# hapcan-dali.net
KiCad netlist of a schematic drawn in EAGLE
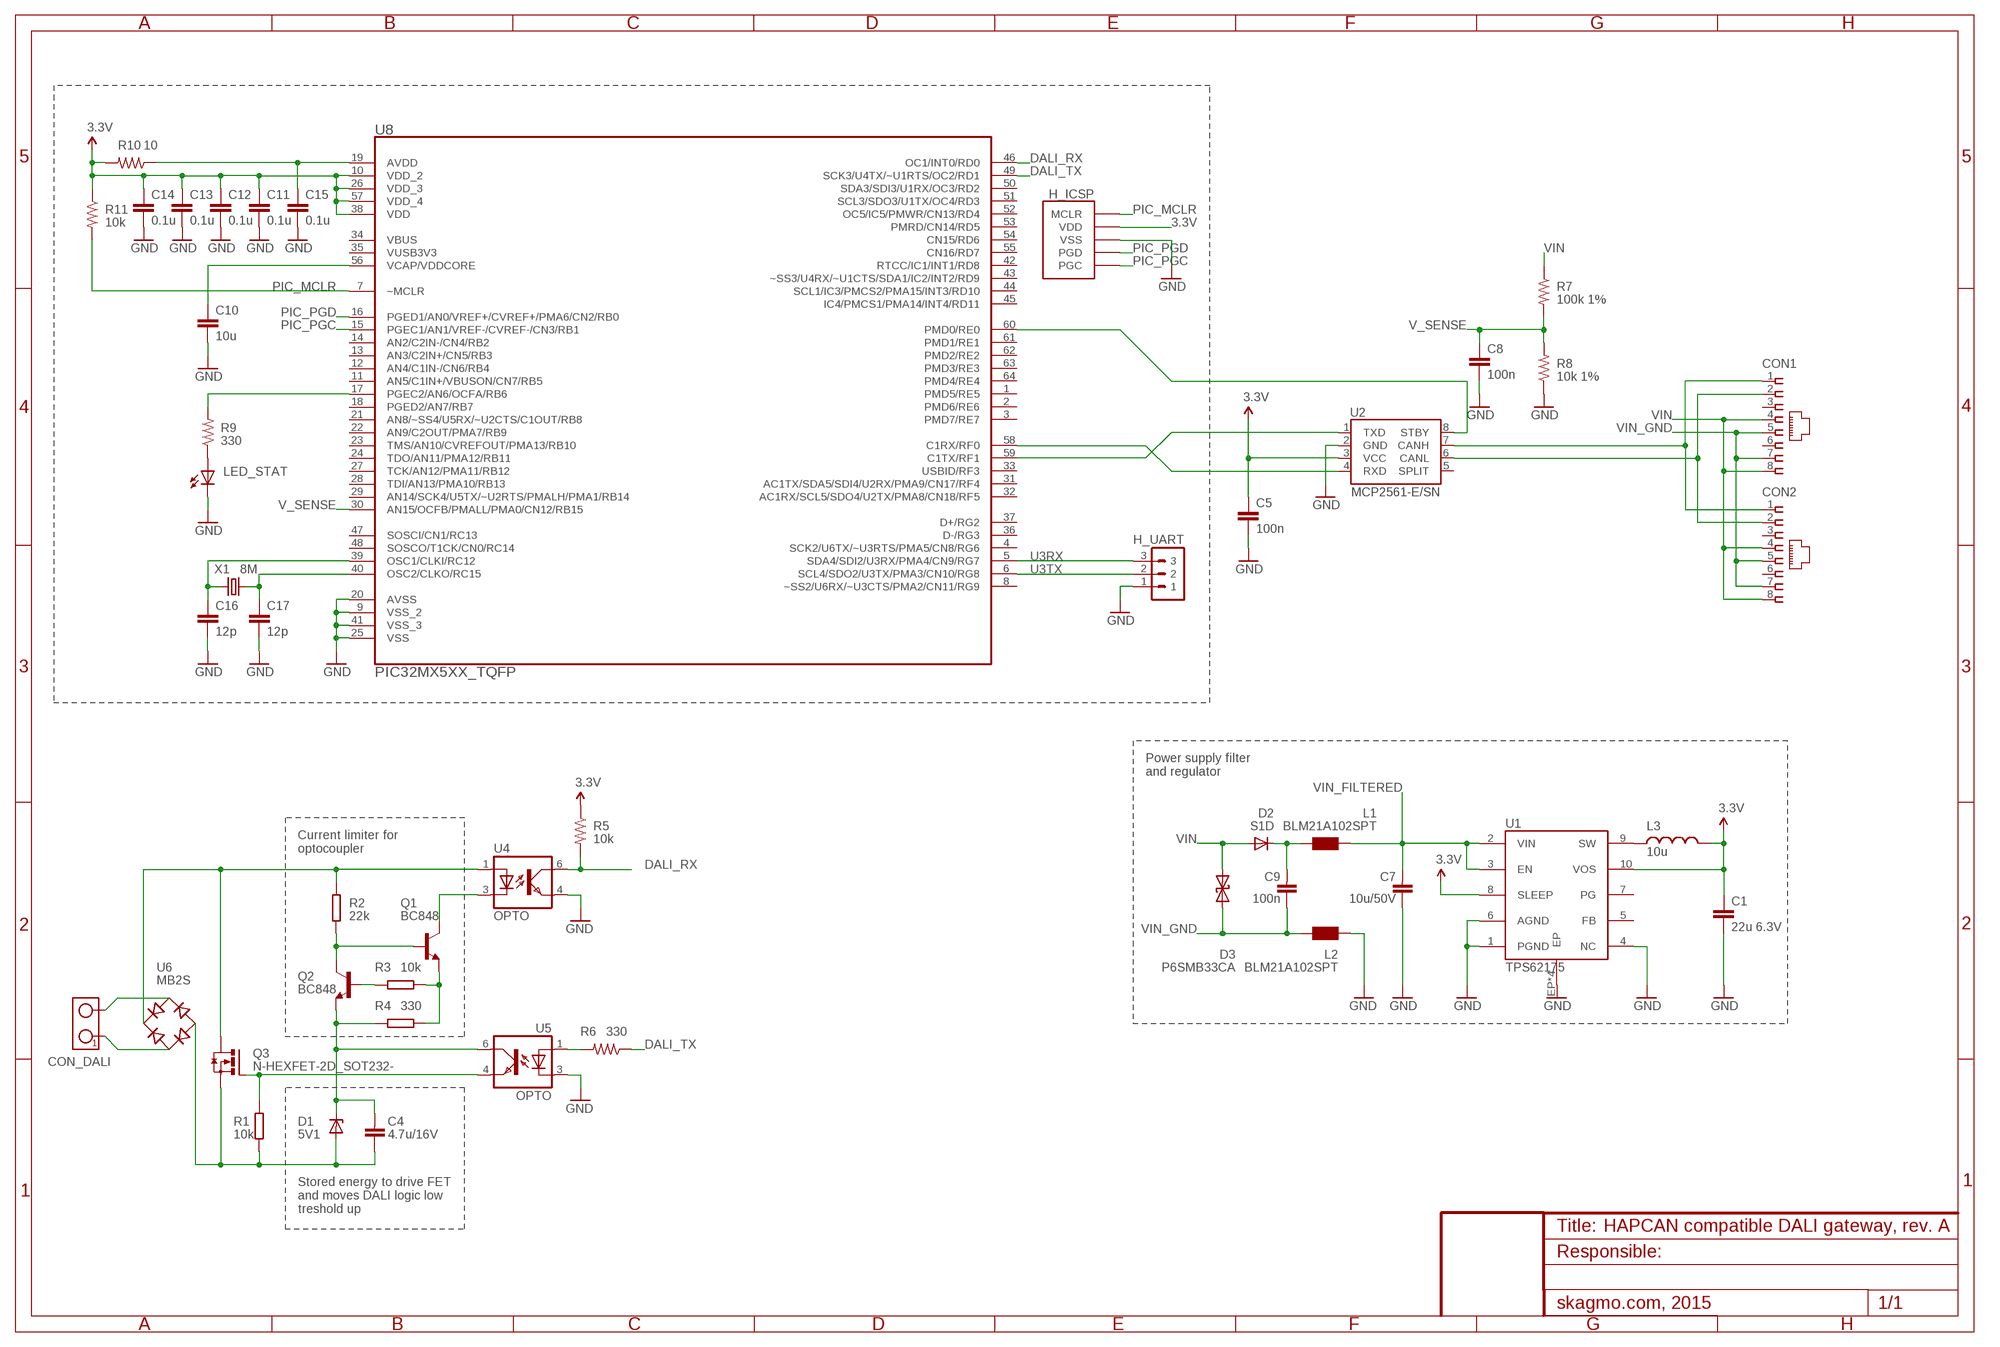
[diagram p0: schematic, sheet 1]

(export (version "E")
  (design (tool "Eeschema 10.0.6"))
  (components
    (comp (ref "C1")
      (value "22u 6.3V")
      (footprint "eagle-import:0805")
      (libsource (lib "eagle-import") (part "CAP0805"))
    )
    (comp (ref "C4")
      (value "4.7u/16V")
      (footprint "eagle-import:0805")
      (libsource (lib "eagle-import") (part "CAPACITOR0805"))
    )
    (comp (ref "C5")
      (value "100n")
      (footprint "eagle-import:0603")
      (libsource (lib "eagle-import") (part "CAP0603"))
    )
    (comp (ref "C7")
      (value "10u/50V")
      (footprint "eagle-import:1210")
      (libsource (lib "eagle-import") (part "CAPACITOR1210"))
    )
    (comp (ref "C8")
      (value "100n")
      (footprint "eagle-import:0603")
      (libsource (lib "eagle-import") (part "CAP0603"))
    )
    (comp (ref "C9")
      (value "100n")
      (footprint "eagle-import:0805")
      (libsource (lib "eagle-import") (part "CAPACITOR0805"))
    )
    (comp (ref "C10")
      (value "10u")
      (footprint "eagle-import:0805")
      (libsource (lib "eagle-import") (part "CAP0805"))
    )
    (comp (ref "C11")
      (value "0.1u")
      (footprint "eagle-import:0603")
      (libsource (lib "eagle-import") (part "CAP0603"))
    )
    (comp (ref "C12")
      (value "0.1u")
      (footprint "eagle-import:0603")
      (libsource (lib "eagle-import") (part "CAP0603"))
    )
    (comp (ref "C13")
      (value "0.1u")
      (footprint "eagle-import:0603")
      (libsource (lib "eagle-import") (part "CAP0603"))
    )
    (comp (ref "C14")
      (value "0.1u")
      (footprint "eagle-import:0603")
      (libsource (lib "eagle-import") (part "CAP0603"))
    )
    (comp (ref "C15")
      (value "0.1u")
      (footprint "eagle-import:0603")
      (libsource (lib "eagle-import") (part "CAP0603"))
    )
    (comp (ref "C16")
      (value "12p")
      (footprint "eagle-import:0603")
      (libsource (lib "eagle-import") (part "CAP0603"))
    )
    (comp (ref "C17")
      (value "12p")
      (footprint "eagle-import:0603")
      (libsource (lib "eagle-import") (part "CAP0603"))
    )
    (comp (ref "CON1")
      (value "RJ45-SOCKET")
      (footprint "eagle-import:RJ45-PCB-SOCKET")
      (libsource (lib "eagle-import") (part "RJ45-SOCKET"))
    )
    (comp (ref "CON2")
      (value "RJ45-SOCKET")
      (footprint "eagle-import:RJ45-PCB-SOCKET")
      (libsource (lib "eagle-import") (part "RJ45-SOCKET"))
    )
    (comp (ref "CON_DALI")
      (value "TERMINAL-2")
      (footprint "eagle-import:ARK2-5X10,5MM")
      (libsource (lib "eagle-import") (part "TERMINAL-2-5X10,5MM"))
    )
    (comp (ref "D1")
      (value "5V1")
      (footprint "eagle-import:SOT23")
      (libsource (lib "eagle-import") (part "ZENER-DIODESOT23"))
    )
    (comp (ref "D2")
      (value "S1D")
      (footprint "eagle-import:DO-214")
      (libsource (lib "eagle-import") (part "DIODE_DO-214"))
    )
    (comp (ref "D3")
      (value "P6SMB33CA")
      (footprint "eagle-import:DO-214_TRANSIL2")
      (libsource (lib "eagle-import") (part "DIODE_TRANSIL2"))
    )
    (comp (ref "H_ICSP")
      (value "H1X5_ICSP")
      (footprint "eagle-import:H1X5_2MM")
      (libsource (lib "eagle-import") (part "H1X5_ICSP"))
    )
    (comp (ref "H_UART")
      (value "H1X3_XH")
      (footprint "eagle-import:CON_B3B-XH-A")
      (libsource (lib "eagle-import") (part "H1X3_XH"))
    )
    (comp (ref "L1")
      (value "BLM21A102SPT")
      (footprint "eagle-import:0805")
      (libsource (lib "eagle-import") (part "CHOKE0805"))
    )
    (comp (ref "L2")
      (value "BLM21A102SPT")
      (footprint "eagle-import:0805")
      (libsource (lib "eagle-import") (part "CHOKE0805"))
    )
    (comp (ref "L3")
      (value "10u")
      (footprint "eagle-import:IND-SRN3015")
      (libsource (lib "eagle-import") (part "INDUCTOR_SRN3015"))
    )
    (comp (ref "LED_STAT")
      (value "LEDCHIPLED_0805")
      (footprint "eagle-import:CHIPLED_0805")
      (libsource (lib "eagle-import") (part "LEDCHIPLED_0805"))
    )
    (comp (ref "Q1")
      (value "BC848")
      (footprint "eagle-import:SOT23")
      (libsource (lib "eagle-import") (part "BC848"))
    )
    (comp (ref "Q2")
      (value "BC848")
      (footprint "eagle-import:SOT23")
      (libsource (lib "eagle-import") (part "BC848"))
    )
    (comp (ref "Q3")
      (value "N-HEXFET-2D_SOT232-")
      (footprint "eagle-import:SOT223")
      (libsource (lib "eagle-import") (part "N-HEXFET-2D_?-SOT232"))
    )
    (comp (ref "R1")
      (value "10k")
      (footprint "eagle-import:0805")
      (libsource (lib "eagle-import") (part "HAPCAN_devices - UNIV3_RESISTOR0805"))
    )
    (comp (ref "R2")
      (value "22k")
      (footprint "eagle-import:0805")
      (libsource (lib "eagle-import") (part "HAPCAN_devices - UNIV3_RESISTOR0805"))
    )
    (comp (ref "R3")
      (value "10k")
      (footprint "eagle-import:0805")
      (libsource (lib "eagle-import") (part "HAPCAN_devices - UNIV3_RESISTOR0805"))
    )
    (comp (ref "R4")
      (value "330")
      (footprint "eagle-import:0805")
      (libsource (lib "eagle-import") (part "HAPCAN_devices - UNIV3_RESISTOR0805"))
    )
    (comp (ref "R5")
      (value "10k")
      (footprint "eagle-import:0603")
      (libsource (lib "eagle-import") (part "RESISTOR0603"))
    )
    (comp (ref "R6")
      (value "330")
      (footprint "eagle-import:0603")
      (libsource (lib "eagle-import") (part "RESISTOR0603"))
    )
    (comp (ref "R7")
      (value "100k 1%")
      (footprint "eagle-import:0603")
      (libsource (lib "eagle-import") (part "RESISTOR0603"))
    )
    (comp (ref "R8")
      (value "10k 1%")
      (footprint "eagle-import:0603")
      (libsource (lib "eagle-import") (part "RESISTOR0603"))
    )
    (comp (ref "R9")
      (value "330")
      (footprint "eagle-import:0603")
      (libsource (lib "eagle-import") (part "RESISTOR0603"))
    )
    (comp (ref "R10")
      (value "10")
      (footprint "eagle-import:0603")
      (libsource (lib "eagle-import") (part "RESISTOR0603"))
    )
    (comp (ref "R11")
      (value "10k")
      (footprint "eagle-import:0603")
      (libsource (lib "eagle-import") (part "RESISTOR0603"))
    )
    (comp (ref "U1")
      (value "TPS62175")
      (footprint "eagle-import:WSON-10")
      (libsource (lib "eagle-import") (part "TPS62175"))
    )
    (comp (ref "U2")
      (value "MCP2561-E/SN")
      (footprint "eagle-import:SO-08")
      (libsource (lib "eagle-import") (part "MCP2561-E/SN"))
    )
    (comp (ref "U4")
      (value "OPTO")
      (footprint "eagle-import:TLP185")
      (libsource (lib "eagle-import") (part "OPTO"))
    )
    (comp (ref "U5")
      (value "OPTO")
      (footprint "eagle-import:TLP185")
      (libsource (lib "eagle-import") (part "OPTO"))
    )
    (comp (ref "U6")
      (value "MB2S")
      (footprint "eagle-import:SOIC-4")
      (libsource (lib "eagle-import") (part "MBS2"))
    )
    (comp (ref "U8")
      (value "PIC32MX5XX_TQFP")
      (footprint "eagle-import:TQFP64")
      (libsource (lib "eagle-import") (part "PIC32MX5XX_TQFP"))
    )
    (comp (ref "X1")
      (value "8M")
      (footprint "eagle-import:TXC-7A")
      (libsource (lib "eagle-import") (part "CRYSTAL_TXC-7A"))
    )
  )
  (nets
    (net (code "1") (name "/DALI_RX") (class "Default")
      (node (ref "R5") (pin "2") (pinfunction "2_2") (pintype "passive"))
      (node (ref "U4") (pin "6") (pinfunction "COL_6") (pintype "passive"))
      (node (ref "U8") (pin "46") (pinfunction "OC1/INT0/RD0_46") (pintype "bidirectional"))
    )
    (net (code "2") (name "/DALI_TX") (class "Default")
      (node (ref "R6") (pin "1") (pinfunction "1_1") (pintype "passive"))
      (node (ref "U8") (pin "49") (pinfunction "SCK3/U4TX/~{U1RTS/OC2/RD1}_49") (pintype "bidirectional"))
    )
    (net (code "3") (name "/PIC_MCLR") (class "Default")
      (node (ref "H_ICSP") (pin "1") (pinfunction "MCLR_1") (pintype "bidirectional"))
      (node (ref "R11") (pin "2") (pinfunction "2_2") (pintype "passive"))
      (node (ref "U8") (pin "7") (pinfunction "~{MCLR}_7") (pintype "input"))
    )
    (net (code "4") (name "/PIC_PGC") (class "Default")
      (node (ref "H_ICSP") (pin "5") (pinfunction "PGC_5") (pintype "bidirectional"))
      (node (ref "U8") (pin "15") (pinfunction "PGEC1/AN1/VREF-/CVREF-/CN3/RB1_15") (pintype "bidirectional"))
    )
    (net (code "5") (name "/PIC_PGD") (class "Default")
      (node (ref "H_ICSP") (pin "4") (pinfunction "PGD_4") (pintype "bidirectional"))
      (node (ref "U8") (pin "16") (pinfunction "PGED1/AN0/VREF+/CVREF+/PMA6/CN2/RB0_16") (pintype "bidirectional"))
    )
    (net (code "6") (name "/U3RX") (class "Default")
      (node (ref "H_UART") (pin "3") (pinfunction "3_3") (pintype "passive"))
      (node (ref "U8") (pin "5") (pinfunction "SDA4/SDI2/U3RX/PMA4/CN9/RG7_5") (pintype "bidirectional"))
    )
    (net (code "7") (name "/U3TX") (class "Default")
      (node (ref "H_UART") (pin "2") (pinfunction "2_2") (pintype "passive"))
      (node (ref "U8") (pin "6") (pinfunction "SCL4/SDO2/U3TX/PMA3/CN10/RG8_6") (pintype "bidirectional"))
    )
    (net (code "8") (name "/VIN") (class "Default")
      (node (ref "CON1") (pin "4") (pinfunction "4_4") (pintype "passive"))
      (node (ref "CON1") (pin "8") (pinfunction "8_8") (pintype "passive"))
      (node (ref "CON2") (pin "4") (pinfunction "4_4") (pintype "passive"))
      (node (ref "CON2") (pin "8") (pinfunction "8_8") (pintype "passive"))
      (node (ref "D2") (pin "A") (pinfunction "A_A") (pintype "passive"))
      (node (ref "D3") (pin "C") (pinfunction "2_C") (pintype "passive"))
      (node (ref "R7") (pin "1") (pinfunction "1_1") (pintype "passive"))
    )
    (net (code "9") (name "/VIN_FILTERED") (class "Default")
      (node (ref "C7") (pin "1") (pinfunction "1_1") (pintype "passive"))
      (node (ref "L1") (pin "1") (pinfunction "1_1") (pintype "passive"))
      (node (ref "U1") (pin "2") (pinfunction "VIN_2") (pintype "bidirectional"))
      (node (ref "U1") (pin "3") (pinfunction "EN_3") (pintype "bidirectional"))
    )
    (net (code "10") (name "/VIN_GND") (class "Default")
      (node (ref "C9") (pin "2") (pinfunction "2_2") (pintype "passive"))
      (node (ref "CON1") (pin "5") (pinfunction "5_5") (pintype "passive"))
      (node (ref "CON1") (pin "7") (pinfunction "7_7") (pintype "passive"))
      (node (ref "CON2") (pin "5") (pinfunction "5_5") (pintype "passive"))
      (node (ref "CON2") (pin "7") (pinfunction "7_7") (pintype "passive"))
      (node (ref "D3") (pin "A") (pinfunction "1_A") (pintype "passive"))
      (node (ref "L2") (pin "2") (pinfunction "2_2") (pintype "passive"))
    )
    (net (code "11") (name "/VUSB3V3") (class "Default")
      (node (ref "U8") (pin "35") (pinfunction "VUSB3V3_35") (pintype "power_in"))
    )
    (net (code "12") (name "/V_SENSE") (class "Default")
      (node (ref "C8") (pin "1") (pinfunction "1_1") (pintype "passive"))
      (node (ref "R7") (pin "2") (pinfunction "2_2") (pintype "passive"))
      (node (ref "R8") (pin "2") (pinfunction "2_2") (pintype "passive"))
      (node (ref "U8") (pin "30") (pinfunction "AN15/OCFB/PMALL/PMA0/CN12/RB15_30") (pintype "bidirectional"))
    )
    (net (code "13") (name "3.3V") (class "Default")
      (node (ref "C1") (pin "1") (pinfunction "1_1") (pintype "passive"))
      (node (ref "C11") (pin "1") (pinfunction "1_1") (pintype "passive"))
      (node (ref "C12") (pin "1") (pinfunction "1_1") (pintype "passive"))
      (node (ref "C13") (pin "1") (pinfunction "1_1") (pintype "passive"))
      (node (ref "C14") (pin "1") (pinfunction "1_1") (pintype "passive"))
      (node (ref "C5") (pin "1") (pinfunction "1_1") (pintype "passive"))
      (node (ref "H_ICSP") (pin "2") (pinfunction "VDD_2") (pintype "power_in"))
      (node (ref "L3") (pin "P$2") (pinfunction "2_P$2") (pintype "passive"))
      (node (ref "R10") (pin "2") (pinfunction "2_2") (pintype "passive"))
      (node (ref "R11") (pin "1") (pinfunction "1_1") (pintype "passive"))
      (node (ref "R5") (pin "1") (pinfunction "1_1") (pintype "passive"))
      (node (ref "U1") (pin "10") (pinfunction "VOS_10") (pintype "bidirectional"))
      (node (ref "U1") (pin "8") (pinfunction "SLEEP_8") (pintype "bidirectional"))
      (node (ref "U2") (pin "3") (pinfunction "VCC_3") (pintype "bidirectional"))
      (node (ref "U8") (pin "10") (pinfunction "VDD_2_10") (pintype "power_in"))
      (node (ref "U8") (pin "26") (pinfunction "VDD_3_26") (pintype "power_in"))
      (node (ref "U8") (pin "38") (pinfunction "VDD_38") (pintype "power_in"))
      (node (ref "U8") (pin "57") (pinfunction "VDD_4_57") (pintype "power_in"))
    )
    (net (code "14") (name "GND") (class "Default")
      (node (ref "C1") (pin "2") (pinfunction "2_2") (pintype "passive"))
      (node (ref "C10") (pin "2") (pinfunction "2_2") (pintype "passive"))
      (node (ref "C11") (pin "2") (pinfunction "2_2") (pintype "passive"))
      (node (ref "C12") (pin "2") (pinfunction "2_2") (pintype "passive"))
      (node (ref "C13") (pin "2") (pinfunction "2_2") (pintype "passive"))
      (node (ref "C14") (pin "2") (pinfunction "2_2") (pintype "passive"))
      (node (ref "C15") (pin "2") (pinfunction "2_2") (pintype "passive"))
      (node (ref "C16") (pin "2") (pinfunction "2_2") (pintype "passive"))
      (node (ref "C17") (pin "2") (pinfunction "2_2") (pintype "passive"))
      (node (ref "C5") (pin "2") (pinfunction "2_2") (pintype "passive"))
      (node (ref "C7") (pin "2") (pinfunction "2_2") (pintype "passive"))
      (node (ref "C8") (pin "2") (pinfunction "2_2") (pintype "passive"))
      (node (ref "H_ICSP") (pin "3") (pinfunction "VSS_3") (pintype "power_in"))
      (node (ref "H_UART") (pin "1") (pinfunction "1_1") (pintype "passive"))
      (node (ref "L2") (pin "1") (pinfunction "1_1") (pintype "passive"))
      (node (ref "LED_STAT") (pin "C") (pinfunction "C_C") (pintype "passive"))
      (node (ref "R8") (pin "1") (pinfunction "1_1") (pintype "passive"))
      (node (ref "U1") (pin "1") (pinfunction "PGND_1") (pintype "bidirectional"))
      (node (ref "U1") (pin "4") (pinfunction "NC_4") (pintype "bidirectional"))
      (node (ref "U1") (pin "6") (pinfunction "AGND_6") (pintype "bidirectional"))
      (node (ref "U1") (pin "EP") (pinfunction "EP_EP") (pintype "bidirectional"))
      (node (ref "U1") (pin "V1") (pinfunction "EP_V1") (pintype "bidirectional"))
      (node (ref "U1") (pin "V2") (pinfunction "EP_V2") (pintype "bidirectional"))
      (node (ref "U1") (pin "V3") (pinfunction "EP_V3") (pintype "bidirectional"))
      (node (ref "U2") (pin "2") (pinfunction "GND_2") (pintype "bidirectional"))
      (node (ref "U4") (pin "4") (pinfunction "EMIT_4") (pintype "passive"))
      (node (ref "U5") (pin "3") (pinfunction "C_3") (pintype "passive"))
      (node (ref "U8") (pin "20") (pinfunction "AVSS_20") (pintype "passive"))
      (node (ref "U8") (pin "25") (pinfunction "VSS_25") (pintype "passive"))
      (node (ref "U8") (pin "41") (pinfunction "VSS_3_41") (pintype "passive"))
      (node (ref "U8") (pin "9") (pinfunction "VSS_2_9") (pintype "passive"))
    )
    (net (code "15") (name "Net-(C9-Pad1)") (class "Default")
      (node (ref "C9") (pin "1") (pinfunction "1_1") (pintype "passive"))
      (node (ref "D2") (pin "C") (pinfunction "C_C") (pintype "passive"))
      (node (ref "L1") (pin "2") (pinfunction "2_2") (pintype "passive"))
    )
    (net (code "16") (name "Net-(D1-A)") (class "Default")
      (node (ref "C4") (pin "2") (pinfunction "2_2") (pintype "passive"))
      (node (ref "D1") (pin "1") (pinfunction "A_1") (pintype "passive"))
      (node (ref "Q3") (pin "3") (pinfunction "S_3") (pintype "passive"))
      (node (ref "R1") (pin "1") (pinfunction "1_1") (pintype "passive"))
      (node (ref "U6") (pin "-") (pinfunction "-_-") (pintype "passive"))
    )
    (net (code "17") (name "Net-(D1-C)") (class "Default")
      (node (ref "C4") (pin "1") (pinfunction "1_1") (pintype "passive"))
      (node (ref "D1") (pin "3") (pinfunction "C_3") (pintype "passive"))
      (node (ref "Q2") (pin "2") (pinfunction "E_2") (pintype "passive"))
      (node (ref "R4") (pin "1") (pinfunction "1_1") (pintype "passive"))
      (node (ref "U5") (pin "6") (pinfunction "COL_6") (pintype "passive"))
    )
    (net (code "18") (name "Net-(L3-1)") (class "Default")
      (node (ref "L3") (pin "P$1") (pinfunction "1_P$1") (pintype "passive"))
      (node (ref "U1") (pin "9") (pinfunction "SW_9") (pintype "bidirectional"))
    )
    (net (code "19") (name "Net-(LED_STAT-PadA)") (class "Default")
      (node (ref "LED_STAT") (pin "A") (pinfunction "A_A") (pintype "passive"))
      (node (ref "R9") (pin "1") (pinfunction "1_1") (pintype "passive"))
    )
    (net (code "20") (name "Net-(Q1-B)") (class "Default")
      (node (ref "Q1") (pin "1") (pinfunction "B_1") (pintype "passive"))
      (node (ref "Q2") (pin "3") (pinfunction "C_3") (pintype "passive"))
      (node (ref "R2") (pin "1") (pinfunction "1_1") (pintype "passive"))
    )
    (net (code "21") (name "Net-(Q1-C)") (class "Default")
      (node (ref "Q1") (pin "3") (pinfunction "C_3") (pintype "passive"))
      (node (ref "U4") (pin "3") (pinfunction "C_3") (pintype "passive"))
    )
    (net (code "22") (name "Net-(Q1-E)") (class "Default")
      (node (ref "Q1") (pin "2") (pinfunction "E_2") (pintype "passive"))
      (node (ref "R3") (pin "1") (pinfunction "1_1") (pintype "passive"))
      (node (ref "R4") (pin "2") (pinfunction "2_2") (pintype "passive"))
    )
    (net (code "23") (name "Net-(Q2-B)") (class "Default")
      (node (ref "Q2") (pin "1") (pinfunction "B_1") (pintype "passive"))
      (node (ref "R3") (pin "2") (pinfunction "2_2") (pintype "passive"))
    )
    (net (code "24") (name "Net-(Q3-G)") (class "Default")
      (node (ref "Q3") (pin "1") (pinfunction "G_1") (pintype "passive"))
      (node (ref "R1") (pin "2") (pinfunction "2_2") (pintype "passive"))
      (node (ref "U5") (pin "4") (pinfunction "EMIT_4") (pintype "passive"))
    )
    (net (code "25") (name "Net-(U2-CANH)") (class "Default")
      (node (ref "CON1") (pin "1") (pinfunction "1_1") (pintype "passive"))
      (node (ref "CON2") (pin "1") (pinfunction "1_1") (pintype "passive"))
      (node (ref "U2") (pin "7") (pinfunction "CANH_7") (pintype "bidirectional"))
    )
    (net (code "26") (name "Net-(U2-CANL)") (class "Default")
      (node (ref "CON1") (pin "2") (pinfunction "2_2") (pintype "passive"))
      (node (ref "CON2") (pin "2") (pinfunction "2_2") (pintype "passive"))
      (node (ref "U2") (pin "6") (pinfunction "CANL_6") (pintype "bidirectional"))
    )
    (net (code "27") (name "Net-(U2-RXD)") (class "Default")
      (node (ref "U2") (pin "4") (pinfunction "RXD_4") (pintype "bidirectional"))
      (node (ref "U8") (pin "58") (pinfunction "C1RX/RF0_58") (pintype "bidirectional"))
    )
    (net (code "28") (name "Net-(U2-STBY)") (class "Default")
      (node (ref "U2") (pin "8") (pinfunction "STBY_8") (pintype "bidirectional"))
      (node (ref "U8") (pin "60") (pinfunction "PMD0/RE0_60") (pintype "bidirectional"))
    )
    (net (code "29") (name "Net-(U2-TXD)") (class "Default")
      (node (ref "U2") (pin "1") (pinfunction "TXD_1") (pintype "bidirectional"))
      (node (ref "U8") (pin "59") (pinfunction "C1TX/RF1_59") (pintype "bidirectional"))
    )
    (net (code "30") (name "Net-(U4-A)") (class "Default")
      (node (ref "Q3") (pin "2") (pinfunction "D_2") (pintype "passive"))
      (node (ref "Q3") (pin "4") (pinfunction "D_4") (pintype "passive"))
      (node (ref "R2") (pin "2") (pinfunction "2_2") (pintype "passive"))
      (node (ref "U4") (pin "1") (pinfunction "A_1") (pintype "passive"))
      (node (ref "U6") (pin "+") (pinfunction "+_+") (pintype "passive"))
    )
    (net (code "31") (name "Net-(U5-A)") (class "Default")
      (node (ref "R6") (pin "2") (pinfunction "2_2") (pintype "passive"))
      (node (ref "U5") (pin "1") (pinfunction "A_1") (pintype "passive"))
    )
    (net (code "32") (name "Net-(U6-AC1)") (class "Default")
      (node (ref "CON_DALI") (pin "1") (pinfunction "1_1") (pintype "passive"))
      (node (ref "U6") (pin "~1") (pinfunction "AC1_~1") (pintype "passive"))
    )
    (net (code "33") (name "Net-(U6-AC2)") (class "Default")
      (node (ref "CON_DALI") (pin "2") (pinfunction "2_2") (pintype "passive"))
      (node (ref "U6") (pin "~2") (pinfunction "AC2_~2") (pintype "passive"))
    )
    (net (code "34") (name "Net-(U8-AVDD)") (class "Default")
      (node (ref "C15") (pin "1") (pinfunction "1_1") (pintype "passive"))
      (node (ref "R10") (pin "1") (pinfunction "1_1") (pintype "passive"))
      (node (ref "U8") (pin "19") (pinfunction "AVDD_19") (pintype "power_in"))
    )
    (net (code "35") (name "Net-(U8-OSC1{slash}CLKI{slash}RC12)") (class "Default")
      (node (ref "C16") (pin "1") (pinfunction "1_1") (pintype "passive"))
      (node (ref "U8") (pin "39") (pinfunction "OSC1/CLKI/RC12_39") (pintype "bidirectional"))
      (node (ref "X1") (pin "1") (pinfunction "1_1") (pintype "passive"))
    )
    (net (code "36") (name "Net-(U8-OSC2{slash}CLKO{slash}RC15)") (class "Default")
      (node (ref "C17") (pin "1") (pinfunction "1_1") (pintype "passive"))
      (node (ref "U8") (pin "40") (pinfunction "OSC2/CLKO/RC15_40") (pintype "bidirectional"))
      (node (ref "X1") (pin "2") (pinfunction "2_2") (pintype "passive"))
    )
    (net (code "37") (name "Net-(U8-PGEC2{slash}AN6{slash}OCFA{slash}RB6)") (class "Default")
      (node (ref "R9") (pin "2") (pinfunction "2_2") (pintype "passive"))
      (node (ref "U8") (pin "17") (pinfunction "PGEC2/AN6/OCFA/RB6_17") (pintype "bidirectional"))
    )
    (net (code "38") (name "Net-(U8-VCAP{slash}VDDCORE)") (class "Default")
      (node (ref "C10") (pin "1") (pinfunction "1_1") (pintype "passive"))
      (node (ref "U8") (pin "56") (pinfunction "VCAP/VDDCORE_56") (pintype "power_in"))
    )
    (net (code "39") (name "unconnected-(CON1-Pad3)") (class "Default")
      (node (ref "CON1") (pin "3") (pinfunction "3_3") (pintype "passive"))
    )
    (net (code "40") (name "unconnected-(CON1-Pad6)") (class "Default")
      (node (ref "CON1") (pin "6") (pinfunction "6_6") (pintype "passive"))
    )
    (net (code "41") (name "unconnected-(CON2-Pad3)") (class "Default")
      (node (ref "CON2") (pin "3") (pinfunction "3_3") (pintype "passive"))
    )
    (net (code "42") (name "unconnected-(CON2-Pad6)") (class "Default")
      (node (ref "CON2") (pin "6") (pinfunction "6_6") (pintype "passive"))
    )
    (net (code "43") (name "unconnected-(U1-FB-Pad5)") (class "Default")
      (node (ref "U1") (pin "5") (pinfunction "FB_5") (pintype "bidirectional"))
    )
    (net (code "44") (name "unconnected-(U1-PG-Pad7)") (class "Default")
      (node (ref "U1") (pin "7") (pinfunction "PG_7") (pintype "bidirectional"))
    )
    (net (code "45") (name "unconnected-(U2-SPLIT-Pad5)") (class "Default")
      (node (ref "U2") (pin "5") (pinfunction "SPLIT_5") (pintype "bidirectional"))
    )
    (net (code "46") (name "unconnected-(U8-AC1RX{slash}SCL5{slash}SDO4{slash}U2TX{slash}PMA8{slash}CN18{slash}RF5-Pad32)") (class "Default")
      (node (ref "U8") (pin "32") (pinfunction "AC1RX/SCL5/SDO4/U2TX/PMA8/CN18/RF5_32") (pintype "bidirectional"))
    )
    (net (code "47") (name "unconnected-(U8-AC1TX{slash}SDA5{slash}SDI4{slash}U2RX{slash}PMA9{slash}CN17{slash}RF4-Pad31)") (class "Default")
      (node (ref "U8") (pin "31") (pinfunction "AC1TX/SDA5/SDI4/U2RX/PMA9/CN17/RF4_31") (pintype "bidirectional"))
    )
    (net (code "48") (name "unconnected-(U8-AN2{slash}C2IN-{slash}CN4{slash}RB2-Pad14)") (class "Default")
      (node (ref "U8") (pin "14") (pinfunction "AN2/C2IN-/CN4/RB2_14") (pintype "bidirectional"))
    )
    (net (code "49") (name "unconnected-(U8-AN3{slash}C2IN+{slash}CN5{slash}RB3-Pad13)") (class "Default")
      (node (ref "U8") (pin "13") (pinfunction "AN3/C2IN+/CN5/RB3_13") (pintype "bidirectional"))
    )
    (net (code "50") (name "unconnected-(U8-AN4{slash}C1IN-{slash}CN6{slash}RB4-Pad12)") (class "Default")
      (node (ref "U8") (pin "12") (pinfunction "AN4/C1IN-/CN6/RB4_12") (pintype "bidirectional"))
    )
    (net (code "51") (name "unconnected-(U8-AN5{slash}C1IN+{slash}VBUSON{slash}CN7{slash}RB5-Pad11)") (class "Default")
      (node (ref "U8") (pin "11") (pinfunction "AN5/C1IN+/VBUSON/CN7/RB5_11") (pintype "bidirectional"))
    )
    (net (code "52") (name "unconnected-(U8-AN8{slash}~{SS4{slash}U5RX{slash}}U2CTS{slash}C1OUT{slash}RB8-Pad21)") (class "Default")
      (node (ref "U8") (pin "21") (pinfunction "AN8/~{SS4/U5RX/}U2CTS/C1OUT/RB8_21") (pintype "bidirectional"))
    )
    (net (code "53") (name "unconnected-(U8-AN9{slash}C2OUT{slash}PMA7{slash}RB9-Pad22)") (class "Default")
      (node (ref "U8") (pin "22") (pinfunction "AN9/C2OUT/PMA7/RB9_22") (pintype "bidirectional"))
    )
    (net (code "54") (name "unconnected-(U8-AN14{slash}SCK4{slash}U5TX{slash}~{U2RTS{slash}PMALH{slash}PMA1{slash}RB14}-Pad29)") (class "Default")
      (node (ref "U8") (pin "29") (pinfunction "AN14/SCK4/U5TX/~{U2RTS/PMALH/PMA1/RB14}_29") (pintype "bidirectional"))
    )
    (net (code "55") (name "unconnected-(U8-CN15{slash}RD6-Pad54)") (class "Default")
      (node (ref "U8") (pin "54") (pinfunction "CN15/RD6_54") (pintype "bidirectional"))
    )
    (net (code "56") (name "unconnected-(U8-CN16{slash}RD7-Pad55)") (class "Default")
      (node (ref "U8") (pin "55") (pinfunction "CN16/RD7_55") (pintype "bidirectional"))
    )
    (net (code "57") (name "unconnected-(U8-D+{slash}RG2-Pad37)") (class "Default")
      (node (ref "U8") (pin "37") (pinfunction "D+/RG2_37") (pintype "bidirectional"))
    )
    (net (code "58") (name "unconnected-(U8-D-{slash}RG3-Pad36)") (class "Default")
      (node (ref "U8") (pin "36") (pinfunction "D-/RG3_36") (pintype "bidirectional"))
    )
    (net (code "59") (name "unconnected-(U8-IC4{slash}PMCS1{slash}PMA14{slash}INT4{slash}RD11-Pad45)") (class "Default")
      (node (ref "U8") (pin "45") (pinfunction "IC4/PMCS1/PMA14/INT4/RD11_45") (pintype "bidirectional"))
    )
    (net (code "60") (name "unconnected-(U8-OC5{slash}IC5{slash}PMWR{slash}CN13{slash}RD4-Pad52)") (class "Default")
      (node (ref "U8") (pin "52") (pinfunction "OC5/IC5/PMWR/CN13/RD4_52") (pintype "bidirectional"))
    )
    (net (code "61") (name "unconnected-(U8-PGED2{slash}AN7{slash}RB7-Pad18)") (class "Default")
      (node (ref "U8") (pin "18") (pinfunction "PGED2/AN7/RB7_18") (pintype "bidirectional"))
    )
    (net (code "62") (name "unconnected-(U8-PMD1{slash}RE1-Pad61)") (class "Default")
      (node (ref "U8") (pin "61") (pinfunction "PMD1/RE1_61") (pintype "bidirectional"))
    )
    (net (code "63") (name "unconnected-(U8-PMD2{slash}RE2-Pad62)") (class "Default")
      (node (ref "U8") (pin "62") (pinfunction "PMD2/RE2_62") (pintype "bidirectional"))
    )
    (net (code "64") (name "unconnected-(U8-PMD3{slash}RE3-Pad63)") (class "Default")
      (node (ref "U8") (pin "63") (pinfunction "PMD3/RE3_63") (pintype "bidirectional"))
    )
    (net (code "65") (name "unconnected-(U8-PMD4{slash}RE4-Pad64)") (class "Default")
      (node (ref "U8") (pin "64") (pinfunction "PMD4/RE4_64") (pintype "bidirectional"))
    )
    (net (code "66") (name "unconnected-(U8-PMD5{slash}RE5-Pad1)") (class "Default")
      (node (ref "U8") (pin "1") (pinfunction "PMD5/RE5_1") (pintype "bidirectional"))
    )
    (net (code "67") (name "unconnected-(U8-PMD6{slash}RE6-Pad2)") (class "Default")
      (node (ref "U8") (pin "2") (pinfunction "PMD6/RE6_2") (pintype "bidirectional"))
    )
    (net (code "68") (name "unconnected-(U8-PMD7{slash}RE7-Pad3)") (class "Default")
      (node (ref "U8") (pin "3") (pinfunction "PMD7/RE7_3") (pintype "bidirectional"))
    )
    (net (code "69") (name "unconnected-(U8-PMRD{slash}CN14{slash}RD5-Pad53)") (class "Default")
      (node (ref "U8") (pin "53") (pinfunction "PMRD/CN14/RD5_53") (pintype "bidirectional"))
    )
    (net (code "70") (name "unconnected-(U8-RTCC{slash}IC1{slash}INT1{slash}RD8-Pad42)") (class "Default")
      (node (ref "U8") (pin "42") (pinfunction "RTCC/IC1/INT1/RD8_42") (pintype "bidirectional"))
    )
    (net (code "71") (name "unconnected-(U8-SCK2{slash}U6TX{slash}~{U3RTS{slash}PMA5{slash}CN8{slash}RG6}-Pad4)") (class "Default")
      (node (ref "U8") (pin "4") (pinfunction "SCK2/U6TX/~{U3RTS/PMA5/CN8/RG6}_4") (pintype "bidirectional"))
    )
    (net (code "72") (name "unconnected-(U8-SCL1{slash}IC3{slash}PMCS2{slash}PMA15{slash}INT3{slash}RD10-Pad44)") (class "Default")
      (node (ref "U8") (pin "44") (pinfunction "SCL1/IC3/PMCS2/PMA15/INT3/RD10_44") (pintype "bidirectional"))
    )
    (net (code "73") (name "unconnected-(U8-SCL3{slash}SDO3{slash}U1TX{slash}OC4{slash}RD3-Pad51)") (class "Default")
      (node (ref "U8") (pin "51") (pinfunction "SCL3/SDO3/U1TX/OC4/RD3_51") (pintype "bidirectional"))
    )
    (net (code "74") (name "unconnected-(U8-SDA3{slash}SDI3{slash}U1RX{slash}OC3{slash}RD2-Pad50)") (class "Default")
      (node (ref "U8") (pin "50") (pinfunction "SDA3/SDI3/U1RX/OC3/RD2_50") (pintype "bidirectional"))
    )
    (net (code "75") (name "unconnected-(U8-SOSCI{slash}CN1{slash}RC13-Pad47)") (class "Default")
      (node (ref "U8") (pin "47") (pinfunction "SOSCI/CN1/RC13_47") (pintype "bidirectional"))
    )
    (net (code "76") (name "unconnected-(U8-SOSCO{slash}T1CK{slash}CN0{slash}RC14-Pad48)") (class "Default")
      (node (ref "U8") (pin "48") (pinfunction "SOSCO/T1CK/CN0/RC14_48") (pintype "bidirectional"))
    )
    (net (code "77") (name "unconnected-(U8-TCK{slash}AN12{slash}PMA11{slash}RB12-Pad27)") (class "Default")
      (node (ref "U8") (pin "27") (pinfunction "TCK/AN12/PMA11/RB12_27") (pintype "bidirectional"))
    )
    (net (code "78") (name "unconnected-(U8-TDI{slash}AN13{slash}PMA10{slash}RB13-Pad28)") (class "Default")
      (node (ref "U8") (pin "28") (pinfunction "TDI/AN13/PMA10/RB13_28") (pintype "bidirectional"))
    )
    (net (code "79") (name "unconnected-(U8-TDO{slash}AN11{slash}PMA12{slash}RB11-Pad24)") (class "Default")
      (node (ref "U8") (pin "24") (pinfunction "TDO/AN11/PMA12/RB11_24") (pintype "bidirectional"))
    )
    (net (code "80") (name "unconnected-(U8-TMS{slash}AN10{slash}CVREFOUT{slash}PMA13{slash}RB10-Pad23)") (class "Default")
      (node (ref "U8") (pin "23") (pinfunction "TMS/AN10/CVREFOUT/PMA13/RB10_23") (pintype "bidirectional"))
    )
    (net (code "81") (name "unconnected-(U8-USBID{slash}RF3-Pad33)") (class "Default")
      (node (ref "U8") (pin "33") (pinfunction "USBID/RF3_33") (pintype "bidirectional"))
    )
    (net (code "82") (name "unconnected-(U8-VBUS-Pad34)") (class "Default")
      (node (ref "U8") (pin "34") (pinfunction "VBUS_34") (pintype "input"))
    )
    (net (code "83") (name "unconnected-(U8-~{SS2{slash}U6RX{slash}}U3CTS{slash}PMA2{slash}CN11{slash}RG9-Pad8)") (class "Default")
      (node (ref "U8") (pin "8") (pinfunction "~{SS2/U6RX/}U3CTS/PMA2/CN11/RG9_8") (pintype "bidirectional"))
    )
    (net (code "84") (name "unconnected-(U8-~{SS3{slash}U4RX{slash}}U1CTS{slash}SDA1{slash}IC2{slash}INT2{slash}RD9-Pad43)") (class "Default")
      (node (ref "U8") (pin "43") (pinfunction "~{SS3/U4RX/}U1CTS/SDA1/IC2/INT2/RD9_43") (pintype "bidirectional"))
    )
  )
)
